# USB_BT-Tastatursch_009.net
KiCad netlist of a schematic drawn in EAGLE
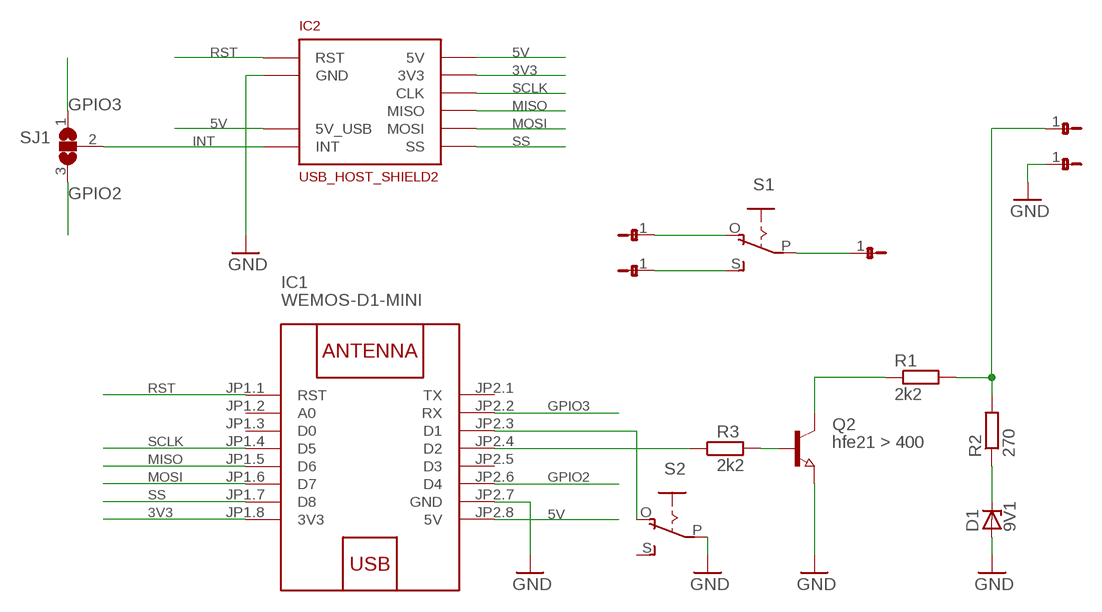
[diagram p0: schematic, sheet 1]

(export (version "E")
  (design (tool "Eeschema 10.0.6"))
  (components
    (comp (ref "D1")
      (value "9V1")
      (footprint "eagle-import:DO34Z7")
      (libsource (lib "eagle-import") (part "ZENER-DIODEDO34-7"))
    )
    (comp (ref "IC1")
      (value "WEMOS-D1-MINI")
      (footprint "eagle-import:WEMOS-D1-MINI_PUR")
      (libsource (lib "eagle-import") (part "WEMOS-D1-MINIWEMOS-D1-MINI-P"))
    )
    (comp (ref "IC2")
      (value "USB_HOST_SHIELD2")
      (footprint "eagle-import:USB_HOST_SHIELD_2")
      (libsource (lib "eagle-import") (part "USB_HOST_SHIELD2"))
    )
    (comp (ref "Q2")
      (value "hfe21 > 400")
      (footprint "eagle-import:SOT23W")
      (libsource (lib "eagle-import") (part "NPN-TRANSISTOR_SOT23W"))
    )
    (comp (ref "R1")
      (value "2k2")
      (footprint "eagle-import:M0805")
      (libsource (lib "eagle-import") (part "R-EU_M0805"))
    )
    (comp (ref "R2")
      (value "270")
      (footprint "eagle-import:M0805")
      (libsource (lib "eagle-import") (part "R-EU_M0805"))
    )
    (comp (ref "R3")
      (value "2k2")
      (footprint "eagle-import:M0805")
      (libsource (lib "eagle-import") (part "R-EU_M0805"))
    )
    (comp (ref "S1")
      (value "EG1218S")
      (footprint "eagle-import:EG1218")
      (libsource (lib "eagle-import") (part "EG1218S"))
    )
    (comp (ref "S2")
      (value "EG1218S")
      (footprint "eagle-import:EG1218")
      (libsource (lib "eagle-import") (part "EG1218S"))
    )
    (comp (ref "SJ1")
      (value "SJ2WSJ_2B")
      (footprint "eagle-import:SJ_2B")
      (libsource (lib "eagle-import") (part "SJ2WSJ_2B"))
    )
    (comp (ref "U$2")
      (value "JP1-1JP1-1C")
      (footprint "eagle-import:JP1-1C")
      (libsource (lib "eagle-import") (part "JP1-1JP1-1C"))
    )
    (comp (ref "U$3")
      (value "JP1-1JP1-1C")
      (footprint "eagle-import:JP1-1C")
      (libsource (lib "eagle-import") (part "JP1-1JP1-1C"))
    )
    (comp (ref "U$4")
      (value "JP1-1JP1-1C")
      (footprint "eagle-import:JP1-1C")
      (libsource (lib "eagle-import") (part "JP1-1JP1-1C"))
    )
    (comp (ref "U$5")
      (value "JP1-1JP1-1C")
      (footprint "eagle-import:JP1-1C")
      (libsource (lib "eagle-import") (part "JP1-1JP1-1C"))
    )
    (comp (ref "U$6")
      (value "JP1-1JP1-1C")
      (footprint "eagle-import:JP1-1C")
      (libsource (lib "eagle-import") (part "JP1-1JP1-1C"))
    )
  )
  (nets
    (net (code "1") (name "/3V3") (class "Default")
      (node (ref "IC1") (pin "JP1.8") (pinfunction "3V3_JP1.8") (pintype "power_in"))
      (node (ref "IC2") (pin "VCC") (pinfunction "3V3_VCC") (pintype "power_in"))
    )
    (net (code "2") (name "/5V") (class "Default")
      (node (ref "IC1") (pin "JP2.8") (pinfunction "5V_JP2.8") (pintype "power_in"))
      (node (ref "IC2") (pin "5V") (pinfunction "5V_5V") (pintype "bidirectional"))
      (node (ref "IC2") (pin "5V_USB") (pinfunction "5V_USB_5V_USB") (pintype "bidirectional"))
    )
    (net (code "3") (name "/GPIO2") (class "Default")
      (node (ref "IC1") (pin "JP2.6") (pinfunction "D4_JP2.6") (pintype "bidirectional"))
      (node (ref "SJ1") (pin "3") (pinfunction "3_3") (pintype "passive"))
    )
    (net (code "4") (name "/GPIO3") (class "Default")
      (node (ref "IC1") (pin "JP2.2") (pinfunction "RX_JP2.2") (pintype "bidirectional"))
      (node (ref "SJ1") (pin "1") (pinfunction "1_1") (pintype "passive"))
    )
    (net (code "5") (name "/INT") (class "Default")
      (node (ref "IC2") (pin "INT") (pinfunction "INT_INT") (pintype "bidirectional"))
      (node (ref "SJ1") (pin "2") (pinfunction "2_2") (pintype "passive"))
    )
    (net (code "6") (name "/MISO") (class "Default")
      (node (ref "IC1") (pin "JP1.5") (pinfunction "D6_JP1.5") (pintype "bidirectional"))
      (node (ref "IC2") (pin "MISO") (pinfunction "MISO_MISO") (pintype "bidirectional"))
    )
    (net (code "7") (name "/MOSI") (class "Default")
      (node (ref "IC1") (pin "JP1.6") (pinfunction "D7_JP1.6") (pintype "bidirectional"))
      (node (ref "IC2") (pin "MOSI") (pinfunction "MOSI_MOSI") (pintype "bidirectional"))
    )
    (net (code "8") (name "/RST") (class "Default")
      (node (ref "IC1") (pin "JP1.1") (pinfunction "RST_JP1.1") (pintype "bidirectional"))
      (node (ref "IC2") (pin "RST") (pinfunction "RST_RST") (pintype "bidirectional"))
      (node (ref "IC2") (pin "RST@1") (pinfunction "RST_RST@1") (pintype "bidirectional"))
    )
    (net (code "9") (name "/SCLK") (class "Default")
      (node (ref "IC1") (pin "JP1.4") (pinfunction "D5_JP1.4") (pintype "bidirectional"))
      (node (ref "IC2") (pin "CLK") (pinfunction "CLK_CLK") (pintype "bidirectional"))
    )
    (net (code "10") (name "/SS") (class "Default")
      (node (ref "IC1") (pin "JP1.7") (pinfunction "D8_JP1.7") (pintype "bidirectional"))
      (node (ref "IC2") (pin "SS") (pinfunction "SS_SS") (pintype "bidirectional"))
    )
    (net (code "11") (name "GND") (class "Default")
      (node (ref "D1") (pin "A") (pinfunction "A_A") (pintype "passive"))
      (node (ref "IC1") (pin "JP2.7") (pinfunction "GND_JP2.7") (pintype "power_in"))
      (node (ref "IC2") (pin "GND") (pinfunction "GND_GND") (pintype "power_in"))
      (node (ref "IC2") (pin "GND@1") (pinfunction "GND_GND@1") (pintype "power_in"))
      (node (ref "Q2") (pin "3") (pinfunction "E_3") (pintype "passive"))
      (node (ref "S2") (pin "P") (pinfunction "P_P") (pintype "passive"))
      (node (ref "U$3") (pin "1") (pinfunction "1_1") (pintype "passive"))
    )
    (net (code "12") (name "Net-(D1-PadC)") (class "Default")
      (node (ref "D1") (pin "C") (pinfunction "C_C") (pintype "passive"))
      (node (ref "R2") (pin "1") (pinfunction "1_1") (pintype "passive"))
    )
    (net (code "13") (name "Net-(IC1-D1)") (class "Default")
      (node (ref "IC1") (pin "JP2.3") (pinfunction "D1_JP2.3") (pintype "bidirectional"))
      (node (ref "S2") (pin "O") (pinfunction "O_O") (pintype "passive"))
    )
    (net (code "14") (name "Net-(IC1-D2)") (class "Default")
      (node (ref "IC1") (pin "JP2.4") (pinfunction "D2_JP2.4") (pintype "bidirectional"))
      (node (ref "R3") (pin "1") (pinfunction "1_1") (pintype "passive"))
    )
    (net (code "15") (name "Net-(Q2-B)") (class "Default")
      (node (ref "Q2") (pin "1") (pinfunction "B_1") (pintype "passive"))
      (node (ref "R3") (pin "2") (pinfunction "2_2") (pintype "passive"))
    )
    (net (code "16") (name "Net-(Q2-C)") (class "Default")
      (node (ref "Q2") (pin "2") (pinfunction "C_2") (pintype "passive"))
      (node (ref "R1") (pin "1") (pinfunction "1_1") (pintype "passive"))
    )
    (net (code "17") (name "Net-(R1-Pad2)") (class "Default")
      (node (ref "R1") (pin "2") (pinfunction "2_2") (pintype "passive"))
      (node (ref "R2") (pin "2") (pinfunction "2_2") (pintype "passive"))
      (node (ref "U$2") (pin "1") (pinfunction "1_1") (pintype "passive"))
    )
    (net (code "18") (name "Net-(S1-PadO)") (class "Default")
      (node (ref "S1") (pin "O") (pinfunction "O_O") (pintype "passive"))
      (node (ref "U$5") (pin "1") (pinfunction "1_1") (pintype "passive"))
    )
    (net (code "19") (name "Net-(S1-PadP)") (class "Default")
      (node (ref "S1") (pin "P") (pinfunction "P_P") (pintype "passive"))
      (node (ref "U$4") (pin "1") (pinfunction "1_1") (pintype "passive"))
    )
    (net (code "20") (name "Net-(S1-PadS)") (class "Default")
      (node (ref "S1") (pin "S") (pinfunction "S_S") (pintype "passive"))
      (node (ref "U$6") (pin "1") (pinfunction "1_1") (pintype "passive"))
    )
    (net (code "21") (name "unconnected-(IC1-A0-PadJP1.2)") (class "Default")
      (node (ref "IC1") (pin "JP1.2") (pinfunction "A0_JP1.2") (pintype "bidirectional"))
    )
    (net (code "22") (name "unconnected-(IC1-D0-PadJP1.3)") (class "Default")
      (node (ref "IC1") (pin "JP1.3") (pinfunction "D0_JP1.3") (pintype "bidirectional"))
    )
    (net (code "23") (name "unconnected-(IC1-D3-PadJP2.5)") (class "Default")
      (node (ref "IC1") (pin "JP2.5") (pinfunction "D3_JP2.5") (pintype "bidirectional"))
    )
    (net (code "24") (name "unconnected-(IC1-TX-PadJP2.1)") (class "Default")
      (node (ref "IC1") (pin "JP2.1") (pinfunction "TX_JP2.1") (pintype "bidirectional"))
    )
    (net (code "25") (name "unconnected-(S2-PadS)") (class "Default")
      (node (ref "S2") (pin "S") (pinfunction "S_S") (pintype "passive"))
    )
  )
)
